# Ignition_Board.net
KiCad netlist of a schematic drawn in EAGLE
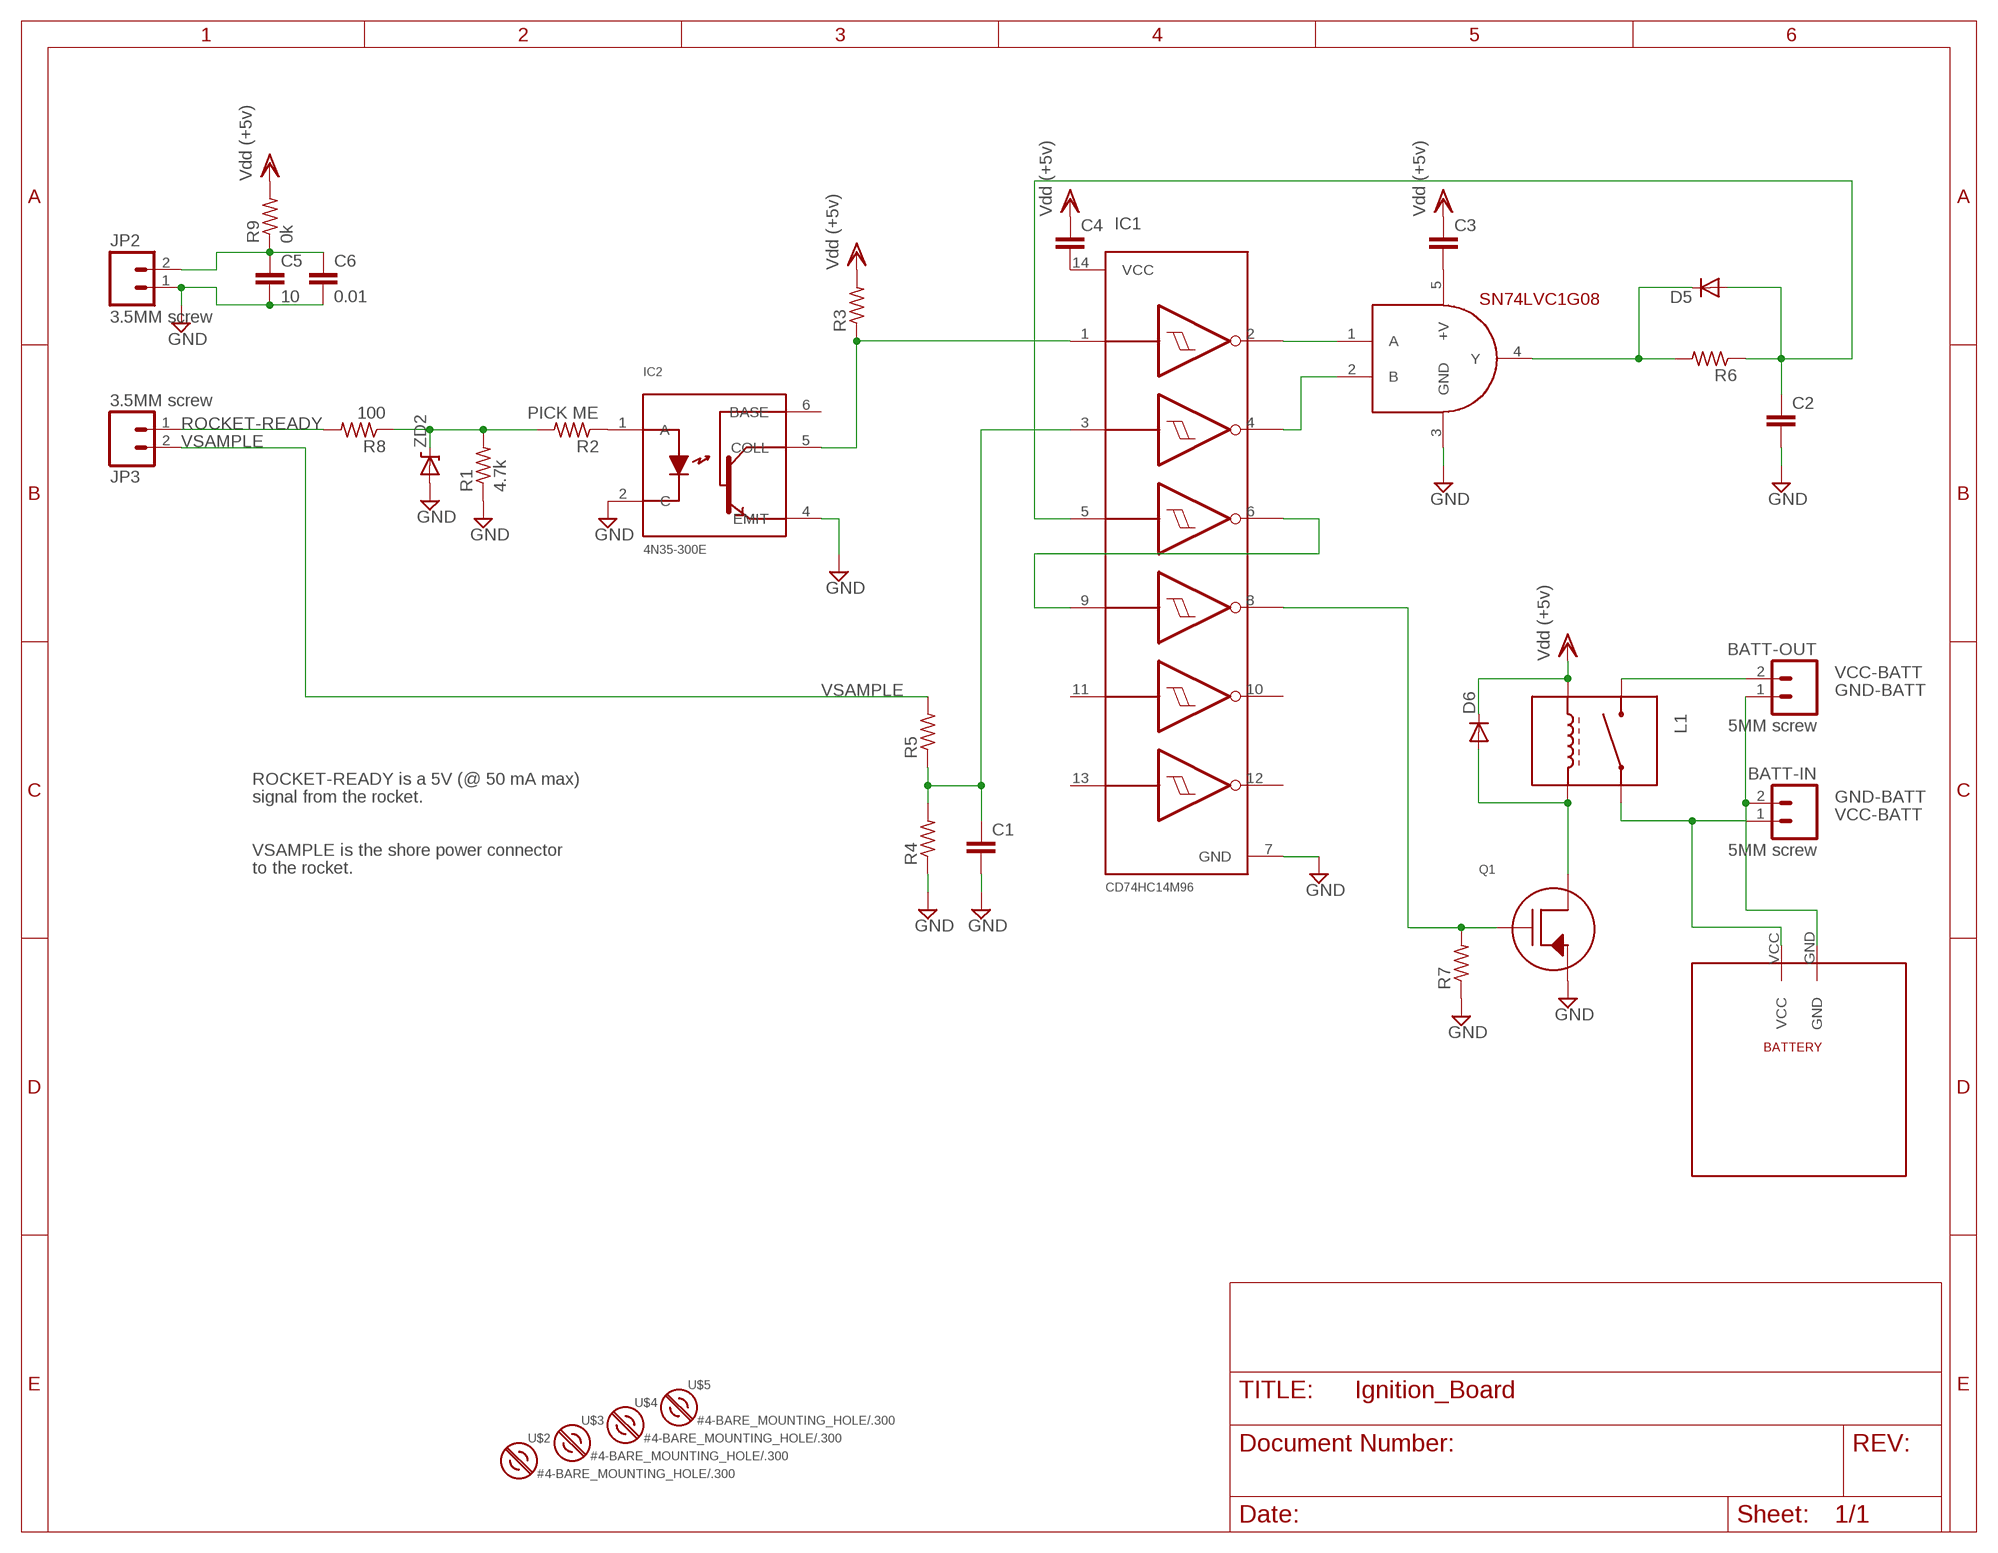
[diagram p0: schematic, sheet 1]

(export (version "E")
  (design (tool "Eeschema 10.0.6"))
  (components
    (comp (ref "BATT-IN")
      (value "5MM screw")
      (footprint "eagle-import:SCREWTERMINAL-5MM-2")
      (libsource (lib "eagle-import") (part "M025MM"))
    )
    (comp (ref "BATT-OUT")
      (value "5MM screw")
      (footprint "eagle-import:SCREWTERMINAL-5MM-2")
      (libsource (lib "eagle-import") (part "M025MM"))
    )
    (comp (ref "C1")
      (value "C-EU0805-B-NOSILK")
      (footprint "eagle-import:0805-B-NOSILK")
      (libsource (lib "eagle-import") (part "C-EU0805-B-NOSILK"))
    )
    (comp (ref "C2")
      (value "C-EU0805-B-NOSILK")
      (footprint "eagle-import:0805-B-NOSILK")
      (libsource (lib "eagle-import") (part "C-EU0805-B-NOSILK"))
    )
    (comp (ref "C3")
      (value "C-EU0805-B-NOSILK")
      (footprint "eagle-import:0805-B-NOSILK")
      (libsource (lib "eagle-import") (part "C-EU0805-B-NOSILK"))
    )
    (comp (ref "C4")
      (value "C-EU0805-B-NOSILK")
      (footprint "eagle-import:0805-B-NOSILK")
      (libsource (lib "eagle-import") (part "C-EU0805-B-NOSILK"))
    )
    (comp (ref "C5")
      (value "10")
      (footprint "eagle-import:0805-B-NOSILK")
      (libsource (lib "eagle-import") (part "C-EU0805-B-NOSILK"))
    )
    (comp (ref "C6")
      (value "0.01")
      (footprint "eagle-import:0805-B-NOSILK")
      (libsource (lib "eagle-import") (part "C-EU0805-B-NOSILK"))
    )
    (comp (ref "D5")
      (value "DIODEPTH")
      (footprint "eagle-import:DIODE-1N4001")
      (libsource (lib "eagle-import") (part "DIODEPTH"))
    )
    (comp (ref "D6")
      (value "DIODEPTH")
      (footprint "eagle-import:DIODE-1N4001")
      (libsource (lib "eagle-import") (part "DIODEPTH"))
    )
    (comp (ref "IC1")
      (value "INVERT GATES")
      (footprint "eagle-import:INVERTSOIC14")
      (libsource (lib "eagle-import") (part "HEX_INV_SHMITT_TRIG"))
    )
    (comp (ref "IC2")
      (value "OPTOISOLATOR")
      (footprint "eagle-import:4N35-300E")
      (libsource (lib "eagle-import") (part "OPTOISOLATOR"))
    )
    (comp (ref "JP2")
      (value "3.5MM screw")
      (footprint "eagle-import:SCREWTERMINAL-3.5MM-2")
      (libsource (lib "eagle-import") (part "M023.5MM"))
    )
    (comp (ref "JP3")
      (value "3.5MM screw")
      (footprint "eagle-import:SCREWTERMINAL-3.5MM-2")
      (libsource (lib "eagle-import") (part "M023.5MM"))
    )
    (comp (ref "L1")
      (value "RELAY")
      (footprint "eagle-import:G5T-1A")
      (libsource (lib "eagle-import") (part "RELAY"))
    )
    (comp (ref "Q1")
      (value "NMOSFET")
      (footprint "eagle-import:FETSO-8")
      (libsource (lib "eagle-import") (part "NMOSFET"))
    )
    (comp (ref "R1")
      (value "4.7k")
      (footprint "eagle-import:0805-B-NOSILK")
      (libsource (lib "eagle-import") (part "R-US_0805-B-NOSILK"))
    )
    (comp (ref "R2")
      (value "PICK ME")
      (footprint "eagle-import:0805-B-NOSILK")
      (libsource (lib "eagle-import") (part "R-US_0805-B-NOSILK"))
    )
    (comp (ref "R3")
      (value "R-US_0805-B-NOSILK")
      (footprint "eagle-import:0805-B-NOSILK")
      (libsource (lib "eagle-import") (part "R-US_0805-B-NOSILK"))
    )
    (comp (ref "R4")
      (value "R-US_0805-B-NOSILK")
      (footprint "eagle-import:0805-B-NOSILK")
      (libsource (lib "eagle-import") (part "R-US_0805-B-NOSILK"))
    )
    (comp (ref "R5")
      (value "R-US_0805-B-NOSILK")
      (footprint "eagle-import:0805-B-NOSILK")
      (libsource (lib "eagle-import") (part "R-US_0805-B-NOSILK"))
    )
    (comp (ref "R6")
      (value "R-US_0805-B-NOSILK")
      (footprint "eagle-import:0805-B-NOSILK")
      (libsource (lib "eagle-import") (part "R-US_0805-B-NOSILK"))
    )
    (comp (ref "R7")
      (value "R-US_0805-B-NOSILK")
      (footprint "eagle-import:0805-B-NOSILK")
      (libsource (lib "eagle-import") (part "R-US_0805-B-NOSILK"))
    )
    (comp (ref "R8")
      (value "100")
      (footprint "eagle-import:0805-B-NOSILK")
      (libsource (lib "eagle-import") (part "R-US_0805-B-NOSILK"))
    )
    (comp (ref "R9")
      (value "0k")
      (footprint "eagle-import:0805-B-NOSILK")
      (libsource (lib "eagle-import") (part "R-US_0805-B-NOSILK"))
    )
    (comp (ref "U$1")
      (value "AND GATE")
      (footprint "eagle-import:SOT23-5")
      (libsource (lib "eagle-import") (part "SN74LVC1G08"))
    )
    (comp (ref "U$2")
      (value "#4-BARE_MOUNTING_HOLE/.300")
      (footprint "eagle-import:#4_.300-BARE+STD_NUT_OR_STAR_WASHER")
      (libsource (lib "eagle-import") (part "#4-BARE_MOUNTING_HOLE/.300"))
    )
    (comp (ref "U$3")
      (value "#4-BARE_MOUNTING_HOLE/.300")
      (footprint "eagle-import:#4_.300-BARE+STD_NUT_OR_STAR_WASHER")
      (libsource (lib "eagle-import") (part "#4-BARE_MOUNTING_HOLE/.300"))
    )
    (comp (ref "U$4")
      (value "#4-BARE_MOUNTING_HOLE/.300")
      (footprint "eagle-import:#4_.300-BARE+STD_NUT_OR_STAR_WASHER")
      (libsource (lib "eagle-import") (part "#4-BARE_MOUNTING_HOLE/.300"))
    )
    (comp (ref "U$5")
      (value "#4-BARE_MOUNTING_HOLE/.300")
      (footprint "eagle-import:#4_.300-BARE+STD_NUT_OR_STAR_WASHER")
      (libsource (lib "eagle-import") (part "#4-BARE_MOUNTING_HOLE/.300"))
    )
    (comp (ref "U$6")
      (value "BATTERY")
      (footprint "eagle-import:BATT-1")
      (libsource (lib "eagle-import") (part "BATTERY"))
    )
    (comp (ref "ZD2")
      (value "DIODE-ZENERPTH")
      (footprint "eagle-import:DIODE-ZENER")
      (libsource (lib "eagle-import") (part "DIODE-ZENERPTH"))
    )
  )
  (nets
    (net (code "1") (name "/GND-BATT") (class "Default")
      (node (ref "BATT-IN") (pin "2") (pinfunction "2_2") (pintype "passive"))
      (node (ref "BATT-OUT") (pin "1") (pinfunction "1_1") (pintype "passive"))
      (node (ref "U$6") (pin "GND") (pinfunction "GND_GND") (pintype "bidirectional"))
    )
    (net (code "2") (name "/ROCKET-READY") (class "Default")
      (node (ref "R1") (pin "2") (pinfunction "2_2") (pintype "passive"))
      (node (ref "R2") (pin "2") (pinfunction "2_2") (pintype "passive"))
      (node (ref "R8") (pin "1") (pinfunction "1_1") (pintype "passive"))
      (node (ref "ZD2") (pin "P$1") (pinfunction "C_P$1") (pintype "passive"))
    )
    (net (code "3") (name "/VCC-BATT") (class "Default")
      (node (ref "BATT-IN") (pin "1") (pinfunction "1_1") (pintype "passive"))
      (node (ref "BATT-OUT") (pin "2") (pinfunction "2_2") (pintype "passive"))
      (node (ref "L1") (pin "SW1") (pinfunction "SW1_SW1") (pintype "bidirectional"))
      (node (ref "L1") (pin "SW2") (pinfunction "SW2_SW2") (pintype "bidirectional"))
      (node (ref "U$6") (pin "VCC") (pinfunction "VCC_VCC") (pintype "bidirectional"))
    )
    (net (code "4") (name "/VSAMPLE") (class "Default")
      (node (ref "JP3") (pin "2") (pinfunction "2_2") (pintype "passive"))
      (node (ref "R5") (pin "2") (pinfunction "2_2") (pintype "passive"))
    )
    (net (code "5") (name "GND") (class "Default")
      (node (ref "C1") (pin "2") (pinfunction "2_2") (pintype "passive"))
      (node (ref "C2") (pin "2") (pinfunction "2_2") (pintype "passive"))
      (node (ref "C5") (pin "2") (pinfunction "2_2") (pintype "passive"))
      (node (ref "C6") (pin "2") (pinfunction "2_2") (pintype "passive"))
      (node (ref "IC1") (pin "7") (pinfunction "GND_7") (pintype "bidirectional"))
      (node (ref "IC2") (pin "2") (pinfunction "C_2") (pintype "bidirectional"))
      (node (ref "IC2") (pin "4") (pinfunction "EMIT_4") (pintype "bidirectional"))
      (node (ref "JP2") (pin "1") (pinfunction "1_1") (pintype "passive"))
      (node (ref "Q1") (pin "1") (pinfunction "SOURCE_1") (pintype "bidirectional"))
      (node (ref "R1") (pin "1") (pinfunction "1_1") (pintype "passive"))
      (node (ref "R4") (pin "1") (pinfunction "1_1") (pintype "passive"))
      (node (ref "R7") (pin "1") (pinfunction "1_1") (pintype "passive"))
      (node (ref "U$1") (pin "3") (pinfunction "GND_3") (pintype "bidirectional"))
      (node (ref "ZD2") (pin "P$2") (pinfunction "A_P$2") (pintype "passive"))
    )
    (net (code "6") (name "Net-(C5-Pad1)") (class "Default")
      (node (ref "C5") (pin "1") (pinfunction "1_1") (pintype "passive"))
      (node (ref "C6") (pin "1") (pinfunction "1_1") (pintype "passive"))
      (node (ref "JP2") (pin "2") (pinfunction "2_2") (pintype "passive"))
      (node (ref "R9") (pin "1") (pinfunction "1_1") (pintype "passive"))
    )
    (net (code "7") (name "Net-(IC1-1A)") (class "Default")
      (node (ref "IC1") (pin "1") (pinfunction "1A_1") (pintype "input"))
      (node (ref "IC2") (pin "5") (pinfunction "COLL_5") (pintype "bidirectional"))
      (node (ref "R3") (pin "1") (pinfunction "1_1") (pintype "passive"))
    )
    (net (code "8") (name "Net-(IC1-1Y)") (class "Default")
      (node (ref "IC1") (pin "2") (pinfunction "1Y_2") (pintype "output"))
      (node (ref "U$1") (pin "1") (pinfunction "A_1") (pintype "bidirectional"))
    )
    (net (code "9") (name "Net-(IC1-2A)") (class "Default")
      (node (ref "C1") (pin "1") (pinfunction "1_1") (pintype "passive"))
      (node (ref "IC1") (pin "3") (pinfunction "2A_3") (pintype "input"))
      (node (ref "R4") (pin "2") (pinfunction "2_2") (pintype "passive"))
      (node (ref "R5") (pin "1") (pinfunction "1_1") (pintype "passive"))
    )
    (net (code "10") (name "Net-(IC1-2Y)") (class "Default")
      (node (ref "IC1") (pin "4") (pinfunction "2Y_4") (pintype "output"))
      (node (ref "U$1") (pin "2") (pinfunction "B_2") (pintype "bidirectional"))
    )
    (net (code "11") (name "Net-(IC1-3A)") (class "Default")
      (node (ref "C2") (pin "1") (pinfunction "1_1") (pintype "passive"))
      (node (ref "D5") (pin "A") (pinfunction "A_A") (pintype "passive"))
      (node (ref "IC1") (pin "5") (pinfunction "3A_5") (pintype "input"))
      (node (ref "R6") (pin "1") (pinfunction "1_1") (pintype "passive"))
    )
    (net (code "12") (name "Net-(IC1-3Y)") (class "Default")
      (node (ref "IC1") (pin "6") (pinfunction "3Y_6") (pintype "output"))
      (node (ref "IC1") (pin "9") (pinfunction "4A_9") (pintype "input"))
    )
    (net (code "13") (name "Net-(IC1-4Y)") (class "Default")
      (node (ref "IC1") (pin "8") (pinfunction "4Y_8") (pintype "output"))
      (node (ref "Q1") (pin "4") (pinfunction "GATE_4") (pintype "bidirectional"))
      (node (ref "R7") (pin "2") (pinfunction "2_2") (pintype "passive"))
    )
    (net (code "14") (name "Net-(IC1-VCC)") (class "Default")
      (node (ref "C4") (pin "2") (pinfunction "2_2") (pintype "passive"))
      (node (ref "IC1") (pin "14") (pinfunction "VCC_14") (pintype "bidirectional"))
    )
    (net (code "15") (name "Net-(IC2-A)") (class "Default")
      (node (ref "IC2") (pin "1") (pinfunction "A_1") (pintype "bidirectional"))
      (node (ref "R2") (pin "1") (pinfunction "1_1") (pintype "passive"))
    )
    (net (code "16") (name "Net-(JP3-Pad1)") (class "Default")
      (node (ref "JP3") (pin "1") (pinfunction "1_1") (pintype "passive"))
      (node (ref "R8") (pin "2") (pinfunction "2_2") (pintype "passive"))
    )
    (net (code "17") (name "Net-(Q1-DRAIN)") (class "Default")
      (node (ref "D6") (pin "A") (pinfunction "A_A") (pintype "passive"))
      (node (ref "L1") (pin "CIN") (pinfunction "CIN_CIN") (pintype "bidirectional"))
      (node (ref "Q1") (pin "5") (pinfunction "DRAIN_5") (pintype "bidirectional"))
    )
    (net (code "18") (name "Net-(U$1-+V)") (class "Default")
      (node (ref "C3") (pin "2") (pinfunction "2_2") (pintype "passive"))
      (node (ref "U$1") (pin "5") (pinfunction "+V_5") (pintype "bidirectional"))
    )
    (net (code "19") (name "Net-(U$1-Y)") (class "Default")
      (node (ref "D5") (pin "C") (pinfunction "C_C") (pintype "passive"))
      (node (ref "R6") (pin "2") (pinfunction "2_2") (pintype "passive"))
      (node (ref "U$1") (pin "4") (pinfunction "Y_4") (pintype "bidirectional"))
    )
    (net (code "20") (name "Vdd (+5v)") (class "Default")
      (node (ref "C3") (pin "1") (pinfunction "1_1") (pintype "passive"))
      (node (ref "C4") (pin "1") (pinfunction "1_1") (pintype "passive"))
      (node (ref "D6") (pin "C") (pinfunction "C_C") (pintype "passive"))
      (node (ref "L1") (pin "COUT") (pinfunction "COUT_COUT") (pintype "bidirectional"))
      (node (ref "R3") (pin "2") (pinfunction "2_2") (pintype "passive"))
      (node (ref "R9") (pin "2") (pinfunction "2_2") (pintype "passive"))
    )
    (net (code "21") (name "unconnected-(IC1-5A-Pad11)") (class "Default")
      (node (ref "IC1") (pin "11") (pinfunction "5A_11") (pintype "input"))
    )
    (net (code "22") (name "unconnected-(IC1-5Y-Pad10)") (class "Default")
      (node (ref "IC1") (pin "10") (pinfunction "5Y_10") (pintype "output"))
    )
    (net (code "23") (name "unconnected-(IC1-6A-Pad13)") (class "Default")
      (node (ref "IC1") (pin "13") (pinfunction "6A_13") (pintype "input"))
    )
    (net (code "24") (name "unconnected-(IC1-6Y-Pad12)") (class "Default")
      (node (ref "IC1") (pin "12") (pinfunction "6Y_12") (pintype "output"))
    )
    (net (code "25") (name "unconnected-(IC2-BASE-Pad6)") (class "Default")
      (node (ref "IC2") (pin "6") (pinfunction "BASE_6") (pintype "bidirectional"))
    )
  )
)
